# processor.net
KiCad netlist of a schematic drawn in Altium Designer
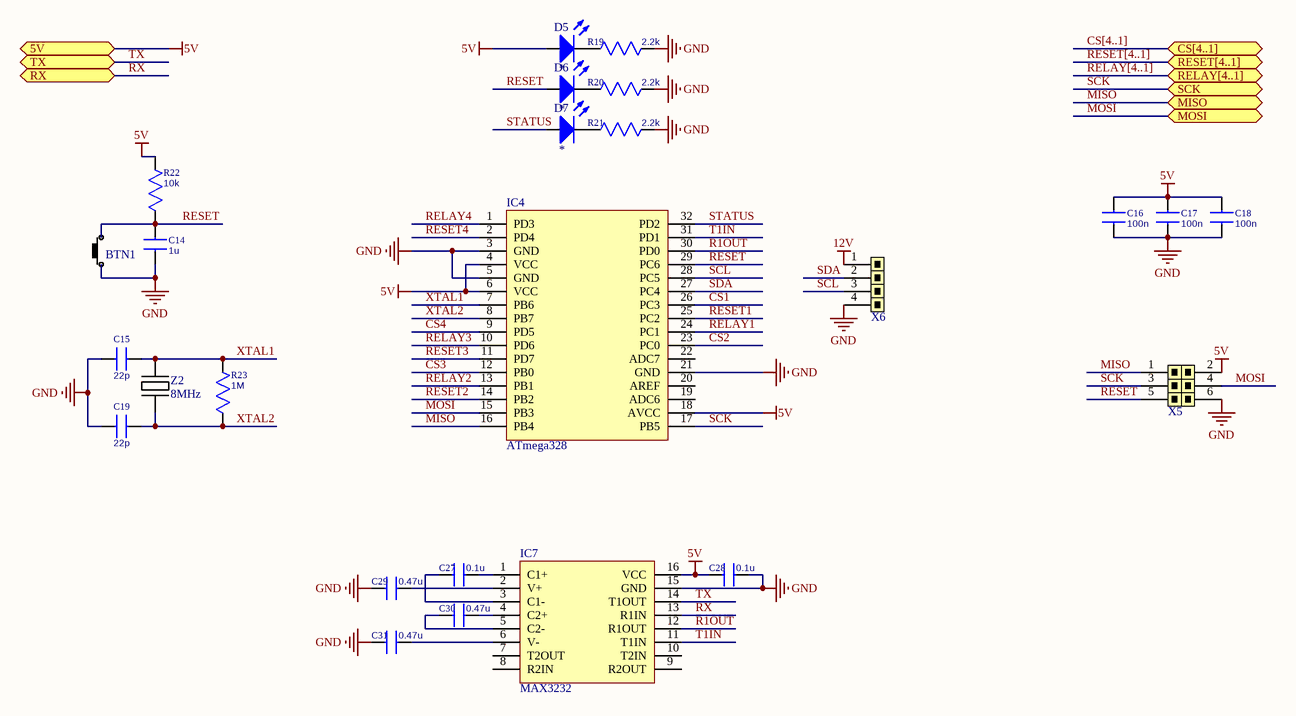
[diagram p0: processor.SchDoc]

(export (version "E")
  (design (tool "Eeschema 10.0.6"))
  (components
    (comp (ref "BTN1")
      (value "Push Button")
      (footprint "PUSH BUTTON")
      (description "Push button")
      (libsource (lib "Light_Music_Integrated_Library") (part "Push Button"))
    )
    (comp (ref "C14")
      (value "1u")
      (footprint "C_0603")
      (description "Capacitor")
      (libsource (lib "AX_Altium_v2.3") (part "C0603"))
    )
    (comp (ref "C15")
      (value "22p")
      (footprint "C_0603")
      (description "Capacitor")
      (libsource (lib "AX_Altium_v2.3") (part "C0603"))
    )
    (comp (ref "C16")
      (value "100n")
      (footprint "C_0603")
      (description "Capacitor")
      (libsource (lib "AX_Altium_v2.3") (part "C0603"))
    )
    (comp (ref "C17")
      (value "100n")
      (footprint "C_0603")
      (description "Capacitor")
      (libsource (lib "AX_Altium_v2.3") (part "C0603"))
    )
    (comp (ref "C18")
      (value "100n")
      (footprint "C_0603")
      (description "Capacitor")
      (libsource (lib "AX_Altium_v2.3") (part "C0603"))
    )
    (comp (ref "C19")
      (value "22p")
      (footprint "C_0603")
      (description "Capacitor")
      (libsource (lib "AX_Altium_v2.3") (part "C0603"))
    )
    (comp (ref "C27")
      (value "0.1u")
      (footprint "C_0805")
      (description "Capacitor")
      (libsource (lib "AX_Altium_v2.3") (part "C0805"))
    )
    (comp (ref "C28")
      (value "0.1u")
      (footprint "C_0805")
      (description "Capacitor")
      (libsource (lib "AX_Altium_v2.3") (part "C0805"))
    )
    (comp (ref "C29")
      (value "0.47u")
      (footprint "C_0805")
      (description "Capacitor")
      (libsource (lib "AX_Altium_v2.3") (part "C0805"))
    )
    (comp (ref "C30")
      (value "0.47u")
      (footprint "C_0805")
      (description "Capacitor")
      (libsource (lib "AX_Altium_v2.3") (part "C0805"))
    )
    (comp (ref "C31")
      (value "0.47u")
      (footprint "C_0805")
      (description "Capacitor")
      (libsource (lib "AX_Altium_v2.3") (part "C0805"))
    )
    (comp (ref "D5")
      (value "*")
      (footprint "LED_5mm")
      (description "Typical INFRARED GaAs LED")
      (libsource (lib "AX_Altium_v2.3") (part "LED_5mm"))
    )
    (comp (ref "D6")
      (value "*")
      (footprint "LED_5mm")
      (description "Typical INFRARED GaAs LED")
      (libsource (lib "AX_Altium_v2.3") (part "LED_5mm"))
    )
    (comp (ref "D7")
      (value "*")
      (footprint "LED_5mm")
      (description "Typical INFRARED GaAs LED")
      (libsource (lib "AX_Altium_v2.3") (part "LED_5mm"))
    )
    (comp (ref "IC4")
      (value "ATmega328")
      (footprint "TQFP-32")
      (description "High Performance, Low Power Atmel AVR 8-Bit Microcontroller")
      (libsource (lib "SmartOutletIntegratedLibrary") (part "ATmega328"))
    )
    (comp (ref "IC7")
      (value "MAX3232")
      (footprint "SSOP-16")
      (description "RS-232 Line Driver/Receiver With ±15-kV ESD Protection")
      (libsource (lib "SmartOutletIntegratedLibrary") (part "MAX3232"))
    )
    (comp (ref "R19")
      (value "2.2k")
      (footprint "R_0603")
      (description "Resistor")
      (libsource (lib "AX_Altium_v2.3") (part "R0603"))
    )
    (comp (ref "R20")
      (value "2.2k")
      (footprint "R_0603")
      (description "Resistor")
      (libsource (lib "AX_Altium_v2.3") (part "R0603"))
    )
    (comp (ref "R21")
      (value "2.2k")
      (footprint "R_0603")
      (description "Resistor")
      (libsource (lib "AX_Altium_v2.3") (part "R0603"))
    )
    (comp (ref "R22")
      (value "10k")
      (footprint "R_0603")
      (description "Resistor")
      (libsource (lib "AX_Altium_v2.3") (part "R0603"))
    )
    (comp (ref "R23")
      (value "1M")
      (footprint "R_0603")
      (description "Resistor")
      (libsource (lib "AX_Altium_v2.3") (part "R0603"))
    )
    (comp (ref "X5")
      (value "PLD-6")
      (footprint "PLD-6")
      (libsource (lib "Light_Music_Integrated_Library") (part "PLD-6"))
    )
    (comp (ref "X6")
      (value "PLS-4")
      (footprint "PLS-4")
      (libsource (lib "Light_Music_Integrated_Library") (part "PLS-4"))
    )
    (comp (ref "Z2")
      (value "8MHz")
      (footprint "HC-49")
      (description "Quartz resonator")
      (libsource (lib "Light_Music_Integrated_Library") (part "XTAL"))
    )
  )
  (nets
    (net (code "1") (name "/CS1") (class "Default")
      (node (ref "IC4") (pin "26") (pinfunction "PC3_26") (pintype "passive"))
    )
    (net (code "2") (name "/CS2") (class "Default")
      (node (ref "IC4") (pin "23") (pinfunction "PC0_23") (pintype "passive"))
    )
    (net (code "3") (name "/CS3") (class "Default")
      (node (ref "IC4") (pin "12") (pinfunction "PB0_12") (pintype "passive"))
    )
    (net (code "4") (name "/CS4") (class "Default")
      (node (ref "IC4") (pin "9") (pinfunction "PD5_9") (pintype "passive"))
    )
    (net (code "6") (name "/MISO") (class "Default")
      (node (ref "IC4") (pin "16") (pinfunction "PB4_16") (pintype "passive"))
      (node (ref "X5") (pin "1") (pinfunction "1_1") (pintype "passive"))
    )
    (net (code "7") (name "/MOSI") (class "Default")
      (node (ref "IC4") (pin "15") (pinfunction "PB3_15") (pintype "passive"))
      (node (ref "X5") (pin "4") (pinfunction "4_4") (pintype "passive"))
    )
    (net (code "8") (name "/R1OUT") (class "Default")
      (node (ref "IC4") (pin "30") (pinfunction "PD0_30") (pintype "passive"))
      (node (ref "IC7") (pin "12") (pinfunction "R1OUT_12") (pintype "passive"))
    )
    (net (code "9") (name "/RELAY1") (class "Default")
      (node (ref "IC4") (pin "24") (pinfunction "PC1_24") (pintype "passive"))
    )
    (net (code "10") (name "/RELAY2") (class "Default")
      (node (ref "IC4") (pin "13") (pinfunction "PB1_13") (pintype "passive"))
    )
    (net (code "11") (name "/RELAY3") (class "Default")
      (node (ref "IC4") (pin "10") (pinfunction "PD6_10") (pintype "passive"))
    )
    (net (code "12") (name "/RELAY4") (class "Default")
      (node (ref "IC4") (pin "1") (pinfunction "PD3_1") (pintype "passive"))
    )
    (net (code "14") (name "/RESET") (class "Default")
      (node (ref "BTN1") (pin "2") (pinfunction "2_2") (pintype "passive"))
      (node (ref "C14") (pin "2") (pintype "passive"))
      (node (ref "D6") (pin "1") (pinfunction "A_1") (pintype "passive"))
      (node (ref "IC4") (pin "29") (pinfunction "PC6_29") (pintype "passive"))
      (node (ref "R22") (pin "2") (pintype "passive"))
      (node (ref "X5") (pin "5") (pinfunction "5_5") (pintype "passive"))
    )
    (net (code "15") (name "/RESET1") (class "Default")
      (node (ref "IC4") (pin "25") (pinfunction "PC2_25") (pintype "passive"))
    )
    (net (code "16") (name "/RESET2") (class "Default")
      (node (ref "IC4") (pin "14") (pinfunction "PB2_14") (pintype "passive"))
    )
    (net (code "17") (name "/RESET3") (class "Default")
      (node (ref "IC4") (pin "11") (pinfunction "PD7_11") (pintype "passive"))
    )
    (net (code "18") (name "/RESET4") (class "Default")
      (node (ref "IC4") (pin "2") (pinfunction "PD4_2") (pintype "passive"))
    )
    (net (code "20") (name "/RX") (class "Default")
      (node (ref "IC7") (pin "13") (pinfunction "R1IN_13") (pintype "passive"))
    )
    (net (code "21") (name "/SCK") (class "Default")
      (node (ref "IC4") (pin "17") (pinfunction "PB5_17") (pintype "passive"))
      (node (ref "X5") (pin "3") (pinfunction "3_3") (pintype "passive"))
    )
    (net (code "22") (name "/SCL") (class "Default")
      (node (ref "IC4") (pin "28") (pinfunction "PC5_28") (pintype "passive"))
      (node (ref "X6") (pin "3") (pinfunction "3_3") (pintype "passive"))
    )
    (net (code "23") (name "/SDA") (class "Default")
      (node (ref "IC4") (pin "27") (pinfunction "PC4_27") (pintype "passive"))
      (node (ref "X6") (pin "2") (pinfunction "2_2") (pintype "passive"))
    )
    (net (code "24") (name "/STATUS") (class "Default")
      (node (ref "D7") (pin "1") (pinfunction "A_1") (pintype "passive"))
      (node (ref "IC4") (pin "32") (pinfunction "PD2_32") (pintype "passive"))
    )
    (net (code "25") (name "/T1IN") (class "Default")
      (node (ref "IC4") (pin "31") (pinfunction "PD1_31") (pintype "passive"))
      (node (ref "IC7") (pin "11") (pinfunction "T1IN_11") (pintype "passive"))
    )
    (net (code "26") (name "/TX") (class "Default")
      (node (ref "IC7") (pin "14") (pinfunction "T1OUT_14") (pintype "passive"))
    )
    (net (code "27") (name "/XTAL1") (class "Default")
      (node (ref "C15") (pin "1") (pintype "passive"))
      (node (ref "IC4") (pin "7") (pinfunction "PB6_7") (pintype "passive"))
      (node (ref "R23") (pin "1") (pintype "passive"))
      (node (ref "Z2") (pin "2") (pinfunction "2_2") (pintype "passive"))
    )
    (net (code "28") (name "/XTAL2") (class "Default")
      (node (ref "C19") (pin "1") (pintype "passive"))
      (node (ref "IC4") (pin "8") (pinfunction "PB7_8") (pintype "passive"))
      (node (ref "R23") (pin "2") (pintype "passive"))
      (node (ref "Z2") (pin "1") (pinfunction "1_1") (pintype "passive"))
    )
    (net (code "29") (name "5V") (class "Default")
      (node (ref "C16") (pin "2") (pintype "passive"))
      (node (ref "C17") (pin "2") (pintype "passive"))
      (node (ref "C18") (pin "2") (pintype "passive"))
      (node (ref "C28") (pin "1") (pintype "passive"))
      (node (ref "D5") (pin "1") (pinfunction "A_1") (pintype "passive"))
      (node (ref "IC4") (pin "18") (pinfunction "AVCC_18") (pintype "passive"))
      (node (ref "IC4") (pin "4") (pinfunction "VCC_4") (pintype "passive"))
      (node (ref "IC4") (pin "6") (pinfunction "VCC_6") (pintype "passive"))
      (node (ref "IC7") (pin "16") (pinfunction "VCC_16") (pintype "passive"))
      (node (ref "R22") (pin "1") (pintype "passive"))
      (node (ref "X5") (pin "2") (pinfunction "2_2") (pintype "passive"))
    )
    (net (code "30") (name "12V") (class "Default")
      (node (ref "X6") (pin "1") (pinfunction "1_1") (pintype "passive"))
    )
    (net (code "31") (name "GND") (class "Default")
      (node (ref "BTN1") (pin "1") (pinfunction "1_1") (pintype "passive"))
      (node (ref "C14") (pin "1") (pintype "passive"))
      (node (ref "C15") (pin "2") (pintype "passive"))
      (node (ref "C16") (pin "1") (pintype "passive"))
      (node (ref "C17") (pin "1") (pintype "passive"))
      (node (ref "C18") (pin "1") (pintype "passive"))
      (node (ref "C19") (pin "2") (pintype "passive"))
      (node (ref "C28") (pin "2") (pintype "passive"))
      (node (ref "C29") (pin "1") (pintype "passive"))
      (node (ref "C31") (pin "1") (pintype "passive"))
      (node (ref "IC4") (pin "21") (pinfunction "GND_21") (pintype "passive"))
      (node (ref "IC4") (pin "3") (pinfunction "GND_3") (pintype "passive"))
      (node (ref "IC4") (pin "5") (pinfunction "GND_5") (pintype "passive"))
      (node (ref "IC7") (pin "15") (pinfunction "GND_15") (pintype "passive"))
      (node (ref "R19") (pin "2") (pintype "passive"))
      (node (ref "R20") (pin "2") (pintype "passive"))
      (node (ref "R21") (pin "2") (pintype "passive"))
      (node (ref "X5") (pin "6") (pinfunction "6_6") (pintype "passive"))
      (node (ref "X6") (pin "4") (pinfunction "4_4") (pintype "passive"))
    )
    (net (code "32") (name "Net-(D5-K)") (class "Default")
      (node (ref "D5") (pin "2") (pinfunction "K_2") (pintype "passive"))
      (node (ref "R19") (pin "1") (pintype "passive"))
    )
    (net (code "33") (name "Net-(D6-K)") (class "Default")
      (node (ref "D6") (pin "2") (pinfunction "K_2") (pintype "passive"))
      (node (ref "R20") (pin "1") (pintype "passive"))
    )
    (net (code "34") (name "Net-(D7-K)") (class "Default")
      (node (ref "D7") (pin "2") (pinfunction "K_2") (pintype "passive"))
      (node (ref "R21") (pin "1") (pintype "passive"))
    )
    (net (code "35") (name "Net-(IC7-C1+)") (class "Default")
      (node (ref "C27") (pin "2") (pintype "passive"))
      (node (ref "IC7") (pin "1") (pinfunction "C1+_1") (pintype "passive"))
    )
    (net (code "36") (name "Net-(IC7-C1-)") (class "Default")
      (node (ref "C27") (pin "1") (pintype "passive"))
      (node (ref "IC7") (pin "3") (pinfunction "C1-_3") (pintype "passive"))
    )
    (net (code "37") (name "Net-(IC7-C2+)") (class "Default")
      (node (ref "C30") (pin "2") (pintype "passive"))
      (node (ref "IC7") (pin "4") (pinfunction "C2+_4") (pintype "passive"))
    )
    (net (code "38") (name "Net-(IC7-C2-)") (class "Default")
      (node (ref "C30") (pin "1") (pintype "passive"))
      (node (ref "IC7") (pin "5") (pinfunction "C2-_5") (pintype "passive"))
    )
    (net (code "39") (name "Net-(IC7-V+)") (class "Default")
      (node (ref "C29") (pin "2") (pintype "passive"))
      (node (ref "IC7") (pin "2") (pinfunction "V+_2") (pintype "passive"))
    )
    (net (code "40") (name "Net-(IC7-V-)") (class "Default")
      (node (ref "C31") (pin "2") (pintype "passive"))
      (node (ref "IC7") (pin "6") (pinfunction "V-_6") (pintype "passive"))
    )
    (net (code "41") (name "unconnected-(IC4-ADC6-Pad19)") (class "Default")
      (node (ref "IC4") (pin "19") (pinfunction "ADC6_19") (pintype "passive"))
    )
    (net (code "42") (name "unconnected-(IC4-ADC7-Pad22)") (class "Default")
      (node (ref "IC4") (pin "22") (pinfunction "ADC7_22") (pintype "passive"))
    )
    (net (code "43") (name "unconnected-(IC4-AREF-Pad20)") (class "Default")
      (node (ref "IC4") (pin "20") (pinfunction "AREF_20") (pintype "passive"))
    )
    (net (code "44") (name "unconnected-(IC7-R2IN-Pad8)") (class "Default")
      (node (ref "IC7") (pin "8") (pinfunction "R2IN_8") (pintype "passive"))
    )
    (net (code "45") (name "unconnected-(IC7-R2OUT-Pad9)") (class "Default")
      (node (ref "IC7") (pin "9") (pinfunction "R2OUT_9") (pintype "passive"))
    )
    (net (code "46") (name "unconnected-(IC7-T2IN-Pad10)") (class "Default")
      (node (ref "IC7") (pin "10") (pinfunction "T2IN_10") (pintype "passive"))
    )
    (net (code "47") (name "unconnected-(IC7-T2OUT-Pad7)") (class "Default")
      (node (ref "IC7") (pin "7") (pinfunction "T2OUT_7") (pintype "passive"))
    )
  )
)
